# HBridge_and_Power.net
KiCad netlist of a schematic drawn in Altium Designer
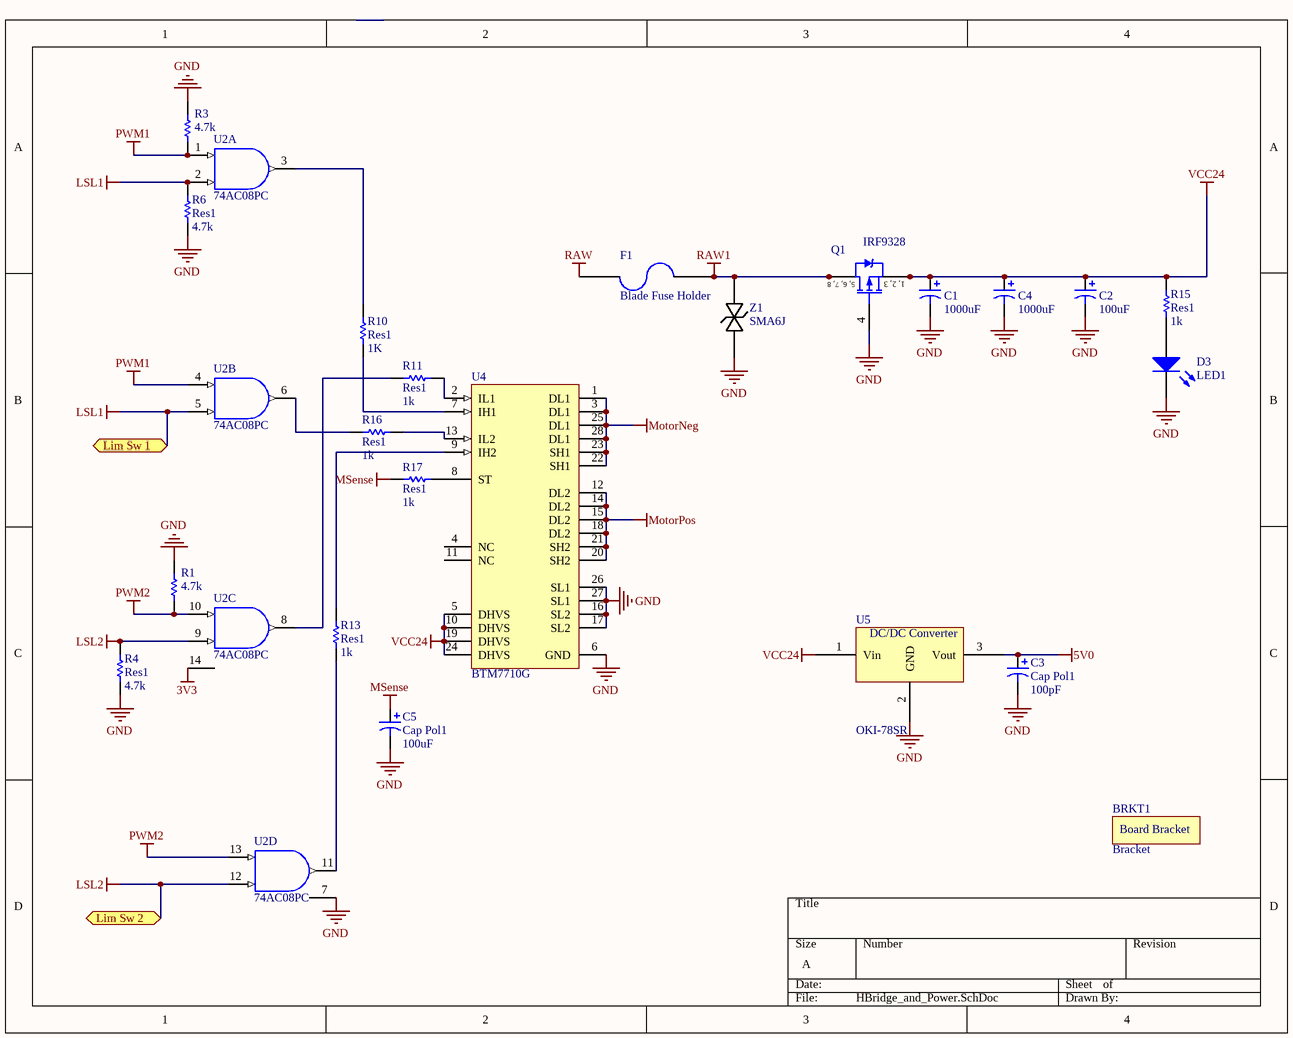
[diagram p0: HBridge_and_Power.SchDoc]

(export (version "E")
  (design (tool "Eeschema 10.0.6"))
  (components
    (comp (ref "BRKT1")
      (value "Bracket")
      (footprint "Board Bracket")
      (description "Board Bracket")
      (libsource (lib "SSS Integrated Library") (part "Bracket"))
    )
    (comp (ref "C1")
      (value "1000uF")
      (footprint "Elec. Cap 5 x 10mm")
      (description "Polarized Capacitor (Radial)")
      (fields (field (name "Comment") "Cap Pol1") (field (name "PUBLISHER") "Altium Limited"))
      (libsource (lib "Miscellaneous Devices") (part "Cap Pol1"))
    )
    (comp (ref "C2")
      (value "100uF")
      (footprint "Elec. Cap 5 x 10mm")
      (description "Polarized Capacitor (Radial)")
      (fields (field (name "Comment") "Cap Pol1") (field (name "PUBLISHER") "Altium Limited"))
      (libsource (lib "Miscellaneous Devices") (part "Cap Pol1"))
    )
    (comp (ref "C3")
      (value "Cap Pol1")
      (footprint "Elec. Cap 5 x 10mm")
      (description "Polarized Capacitor (Radial)")
      (fields (field (name "ALTIUM_VALUE") "100pF") (field (name "PUBLISHER") "Altium Limited"))
      (libsource (lib "Miscellaneous Devices") (part "Cap Pol1"))
    )
    (comp (ref "C4")
      (value "1000uF")
      (footprint "Elec. Cap 5 x 10mm")
      (description "Polarized Capacitor (Radial)")
      (fields (field (name "Comment") "Cap Pol1") (field (name "PUBLISHER") "Altium Limited"))
      (libsource (lib "Miscellaneous Devices") (part "Cap Pol1"))
    )
    (comp (ref "C5")
      (value "Cap Pol1")
      (footprint "Elec. Cap 5 x 10mm")
      (description "Polarized Capacitor (Radial)")
      (fields (field (name "ALTIUM_VALUE") "100uF") (field (name "PUBLISHER") "Altium Limited"))
      (libsource (lib "Miscellaneous Devices") (part "Cap Pol1"))
    )
    (comp (ref "D3")
      (value "LED1")
      (footprint "5mm Rad LED")
      (description "Typical RED GaAs LED")
      (fields (field (name "PUBLISHER") "Altium Limited"))
      (libsource (lib "Miscellaneous Devices") (part "LED1"))
    )
    (comp (ref "F1")
      (value "Blade Fuse Holder")
      (footprint "Fuse Holder")
      (description "PC Auto-Fuse Holder")
      (fields (field (name "MANUFACTURER") "Keystone Electronics") (field (name "PART NUMBER") "3557-15"))
      (libsource (lib "SSS Integrated Library") (part "Fuse - Auto"))
    )
    (comp (ref "Q1")
      (value "IRF9328")
      (footprint "SOIC-8")
      (description "MOSFET P-CH 30V 12A 8-SOIC")
      (libsource (lib "SSS Integrated Library") (part "IRF9328 P-FET"))
    )
    (comp (ref "R1")
      (value "4.7k")
      (footprint "AXIAL-0.3")
      (description "Resistor")
      (fields (field (name "Comment") "Res1") (field (name "PUBLISHER") "Altium Limited"))
      (libsource (lib "Miscellaneous Devices") (part "Res1"))
    )
    (comp (ref "R3")
      (value "4.7k")
      (footprint "AXIAL-0.3")
      (description "Resistor")
      (fields (field (name "Comment") "Res1") (field (name "PUBLISHER") "Altium Limited"))
      (libsource (lib "Miscellaneous Devices") (part "Res1"))
    )
    (comp (ref "R4")
      (value "Res1")
      (footprint "AXIAL-0.3")
      (description "Resistor")
      (fields (field (name "ALTIUM_VALUE") "4.7k") (field (name "PUBLISHER") "Altium Limited"))
      (libsource (lib "Miscellaneous Devices") (part "Res1"))
    )
    (comp (ref "R6")
      (value "Res1")
      (footprint "AXIAL-0.3")
      (description "Resistor")
      (fields (field (name "ALTIUM_VALUE") "4.7k") (field (name "PUBLISHER") "Altium Limited"))
      (libsource (lib "Miscellaneous Devices") (part "Res1"))
    )
    (comp (ref "R10")
      (value "Res1")
      (footprint "AXIAL-0.3")
      (description "Resistor")
      (fields (field (name "ALTIUM_VALUE") "1K") (field (name "PUBLISHER") "Altium Limited"))
      (libsource (lib "Miscellaneous Devices") (part "Res1"))
    )
    (comp (ref "R11")
      (value "Res1")
      (footprint "AXIAL-0.3")
      (description "Resistor")
      (fields (field (name "ALTIUM_VALUE") "1k") (field (name "PUBLISHER") "Altium Limited"))
      (libsource (lib "Miscellaneous Devices") (part "Res1"))
    )
    (comp (ref "R13")
      (value "Res1")
      (footprint "AXIAL-0.3")
      (description "Resistor")
      (fields (field (name "ALTIUM_VALUE") "1k") (field (name "PUBLISHER") "Altium Limited"))
      (libsource (lib "Miscellaneous Devices") (part "Res1"))
    )
    (comp (ref "R15")
      (value "Res1")
      (footprint "AXIAL-0.3")
      (description "Resistor")
      (fields (field (name "ALTIUM_VALUE") "1k") (field (name "PUBLISHER") "Altium Limited"))
      (libsource (lib "Miscellaneous Devices") (part "Res1"))
    )
    (comp (ref "R16")
      (value "Res1")
      (footprint "AXIAL-0.3")
      (description "Resistor")
      (fields (field (name "ALTIUM_VALUE") "1k") (field (name "PUBLISHER") "Altium Limited"))
      (libsource (lib "Miscellaneous Devices") (part "Res1"))
    )
    (comp (ref "R17")
      (value "Res1")
      (footprint "AXIAL-0.3")
      (description "Resistor")
      (fields (field (name "ALTIUM_VALUE") "1k") (field (name "PUBLISHER") "Altium Limited"))
      (libsource (lib "Miscellaneous Devices") (part "Res1"))
    )
    (comp (ref "U2")
      (value "74AC08PC")
      (footprint "N14A")
      (description "Quad 2-Input AND Gate, 14-Pin PDIP, Commercial Grade")
      (fields (field (name "PUBLISHER") "Altium Limited"))
      (libsource (lib "FSC Logic Gate") (part "74AC08PC"))
    )
    (comp (ref "U4")
      (value "BTM7710G")
      (footprint "INF-PG-DSO-28-22_N")
      (description "TrilithIC, 4.5 to 42 V, -40 to 150 degC, PG-DSO-28-22, Reel, Green")
      (fields (field (name "MANUFACTURER") "Infineon"))
      (libsource (lib "Infineon_Power_Motor_Driver") (part "BTM7710G"))
    )
    (comp (ref "U5")
      (value "OKI-78SR")
      (footprint "OKI-78SR")
      (description "5V DC/DC Converter (7805 replacement)")
      (libsource (lib "SSS Integrated Library") (part "7805"))
    )
    (comp (ref "Z1")
      (value "SMA6J")
      (footprint "AXIAL-0.9")
      (description "TVS DIODE 15VWM 24.4VC SMA")
      (fields (field (name "MANUFACTURER") "Micro Commercial Co") (field (name "PARTNUMBER") "SMA6J15CA-TP"))
      (libsource (lib "SSS Integrated Library") (part "Zener - Bidirectional"))
    )
  )
  (nets
    (net (code "1") (name "3V3") (class "Default")
      (node (ref "U2") (pin "14") (pinfunction "VCC_14") (pintype "power_in"))
    )
    (net (code "2") (name "5V0") (class "Default")
      (node (ref "C3") (pin "1") (pinfunction "1_1") (pintype "passive"))
      (node (ref "U5") (pin "3") (pinfunction "Vout_3") (pintype "passive"))
    )
    (net (code "3") (name "GND") (class "Default")
      (node (ref "C1") (pin "2") (pinfunction "2_2") (pintype "passive"))
      (node (ref "C2") (pin "2") (pinfunction "2_2") (pintype "passive"))
      (node (ref "C3") (pin "2") (pinfunction "2_2") (pintype "passive"))
      (node (ref "C4") (pin "2") (pinfunction "2_2") (pintype "passive"))
      (node (ref "C5") (pin "2") (pinfunction "2_2") (pintype "passive"))
      (node (ref "D3") (pin "2") (pinfunction "K_2") (pintype "passive"))
      (node (ref "Q1") (pin "4") (pinfunction "G_4") (pintype "passive"))
      (node (ref "R1") (pin "2") (pinfunction "2_2") (pintype "passive"))
      (node (ref "R3") (pin "2") (pinfunction "2_2") (pintype "passive"))
      (node (ref "R4") (pin "1") (pinfunction "1_1") (pintype "passive"))
      (node (ref "R6") (pin "1") (pinfunction "1_1") (pintype "passive"))
      (node (ref "U2") (pin "7") (pinfunction "GND_7") (pintype "power_in"))
      (node (ref "U4") (pin "16") (pinfunction "SL2_16") (pintype "power_in"))
      (node (ref "U4") (pin "17") (pinfunction "SL2_17") (pintype "power_in"))
      (node (ref "U4") (pin "26") (pinfunction "SL1_26") (pintype "power_in"))
      (node (ref "U4") (pin "27") (pinfunction "SL1_27") (pintype "power_in"))
      (node (ref "U4") (pin "6") (pinfunction "GND_6") (pintype "power_in"))
      (node (ref "U5") (pin "2") (pinfunction "GND_2") (pintype "passive"))
      (node (ref "Z1") (pin "1") (pinfunction "A_1") (pintype "passive"))
    )
    (net (code "4") (name "LSL1") (class "Default")
      (node (ref "R6") (pin "2") (pinfunction "2_2") (pintype "passive"))
      (node (ref "U2") (pin "2") (pinfunction "B_2") (pintype "input"))
      (node (ref "U2") (pin "5") (pinfunction "B_5") (pintype "input"))
    )
    (net (code "5") (name "LSL2") (class "Default")
      (node (ref "R4") (pin "2") (pinfunction "2_2") (pintype "passive"))
      (node (ref "U2") (pin "12") (pinfunction "B_12") (pintype "input"))
      (node (ref "U2") (pin "9") (pinfunction "B_9") (pintype "input"))
    )
    (net (code "6") (name "MSense") (class "Default")
      (node (ref "C5") (pin "1") (pinfunction "1_1") (pintype "passive"))
      (node (ref "R17") (pin "2") (pinfunction "2_2") (pintype "passive"))
    )
    (net (code "7") (name "MotorNeg") (class "Default")
      (node (ref "U4") (pin "1") (pinfunction "DL1_1") (pintype "power_in"))
      (node (ref "U4") (pin "22") (pinfunction "SH1_22") (pintype "power_in"))
      (node (ref "U4") (pin "23") (pinfunction "SH1_23") (pintype "power_in"))
      (node (ref "U4") (pin "25") (pinfunction "DL1_25") (pintype "power_in"))
      (node (ref "U4") (pin "28") (pinfunction "DL1_28") (pintype "power_in"))
      (node (ref "U4") (pin "3") (pinfunction "DL1_3") (pintype "power_in"))
    )
    (net (code "8") (name "MotorPos") (class "Default")
      (node (ref "U4") (pin "12") (pinfunction "DL2_12") (pintype "power_in"))
      (node (ref "U4") (pin "14") (pinfunction "DL2_14") (pintype "power_in"))
      (node (ref "U4") (pin "15") (pinfunction "DL2_15") (pintype "power_in"))
      (node (ref "U4") (pin "18") (pinfunction "DL2_18") (pintype "power_in"))
      (node (ref "U4") (pin "20") (pinfunction "SH2_20") (pintype "power_in"))
      (node (ref "U4") (pin "21") (pinfunction "SH2_21") (pintype "power_in"))
    )
    (net (code "9") (name "Net-(D3-A)") (class "Default")
      (node (ref "D3") (pin "1") (pinfunction "A_1") (pintype "passive"))
      (node (ref "R15") (pin "1") (pinfunction "1_1") (pintype "passive"))
    )
    (net (code "10") (name "Net-(U2A-O)") (class "Default")
      (node (ref "R10") (pin "2") (pinfunction "2_2") (pintype "passive"))
      (node (ref "U2") (pin "3") (pinfunction "O_3") (pintype "output"))
    )
    (net (code "11") (name "Net-(U2B-O)") (class "Default")
      (node (ref "R16") (pin "2") (pinfunction "2_2") (pintype "passive"))
      (node (ref "U2") (pin "6") (pinfunction "O_6") (pintype "output"))
    )
    (net (code "12") (name "Net-(U2C-O)") (class "Default")
      (node (ref "R11") (pin "2") (pinfunction "2_2") (pintype "passive"))
      (node (ref "U2") (pin "8") (pinfunction "O_8") (pintype "output"))
    )
    (net (code "13") (name "Net-(U2D-O)") (class "Default")
      (node (ref "R13") (pin "1") (pinfunction "1_1") (pintype "passive"))
      (node (ref "U2") (pin "11") (pinfunction "O_11") (pintype "output"))
    )
    (net (code "14") (name "Net-(U4-IH1)") (class "Default")
      (node (ref "R10") (pin "1") (pinfunction "1_1") (pintype "passive"))
      (node (ref "U4") (pin "7") (pinfunction "IH1_7") (pintype "input"))
    )
    (net (code "15") (name "Net-(U4-IH2)") (class "Default")
      (node (ref "R13") (pin "2") (pinfunction "2_2") (pintype "passive"))
      (node (ref "U4") (pin "9") (pinfunction "IH2_9") (pintype "input"))
    )
    (net (code "16") (name "Net-(U4-IL1)") (class "Default")
      (node (ref "R11") (pin "1") (pinfunction "1_1") (pintype "passive"))
      (node (ref "U4") (pin "2") (pinfunction "IL1_2") (pintype "input"))
    )
    (net (code "17") (name "Net-(U4-IL2)") (class "Default")
      (node (ref "R16") (pin "1") (pinfunction "1_1") (pintype "passive"))
      (node (ref "U4") (pin "13") (pinfunction "IL2_13") (pintype "input"))
    )
    (net (code "18") (name "Net-(U4-ST)") (class "Default")
      (node (ref "R17") (pin "1") (pinfunction "1_1") (pintype "passive"))
      (node (ref "U4") (pin "8") (pinfunction "ST_8") (pintype "open_collector"))
    )
    (net (code "19") (name "PWM1") (class "Default")
      (node (ref "R3") (pin "1") (pinfunction "1_1") (pintype "passive"))
      (node (ref "U2") (pin "1") (pinfunction "A_1") (pintype "input"))
      (node (ref "U2") (pin "4") (pinfunction "A_4") (pintype "input"))
    )
    (net (code "20") (name "PWM2") (class "Default")
      (node (ref "R1") (pin "1") (pinfunction "1_1") (pintype "passive"))
      (node (ref "U2") (pin "10") (pinfunction "A_10") (pintype "input"))
      (node (ref "U2") (pin "13") (pinfunction "A_13") (pintype "input"))
    )
    (net (code "21") (name "RAW") (class "Default")
      (node (ref "F1") (pin "1") (pinfunction "1_1") (pintype "passive"))
    )
    (net (code "22") (name "RAW1") (class "Default")
      (node (ref "F1") (pin "2") (pinfunction "2_2") (pintype "passive"))
      (node (ref "Q1") (pin "5") (pinfunction "D_5") (pintype "passive"))
      (node (ref "Q1") (pin "6") (pinfunction "D_6") (pintype "passive"))
      (node (ref "Q1") (pin "7") (pinfunction "D_7") (pintype "passive"))
      (node (ref "Q1") (pin "8") (pinfunction "D_8") (pintype "passive"))
      (node (ref "Z1") (pin "2") (pinfunction "K_2") (pintype "passive"))
    )
    (net (code "23") (name "VCC24") (class "Default")
      (node (ref "C1") (pin "1") (pinfunction "1_1") (pintype "passive"))
      (node (ref "C2") (pin "1") (pinfunction "1_1") (pintype "passive"))
      (node (ref "C4") (pin "1") (pinfunction "1_1") (pintype "passive"))
      (node (ref "Q1") (pin "1") (pinfunction "S_1") (pintype "passive"))
      (node (ref "Q1") (pin "2") (pinfunction "S_2") (pintype "passive"))
      (node (ref "Q1") (pin "3") (pinfunction "S_3") (pintype "passive"))
      (node (ref "R15") (pin "2") (pinfunction "2_2") (pintype "passive"))
      (node (ref "U4") (pin "10") (pinfunction "DHVS_10") (pintype "power_in"))
      (node (ref "U4") (pin "19") (pinfunction "DHVS_19") (pintype "power_in"))
      (node (ref "U4") (pin "24") (pinfunction "DHVS_24") (pintype "power_in"))
      (node (ref "U4") (pin "5") (pinfunction "DHVS_5") (pintype "power_in"))
      (node (ref "U5") (pin "1") (pinfunction "Vin_1") (pintype "passive"))
    )
    (net (code "24") (name "unconnected-(U4-NC-Pad4)") (class "Default")
      (node (ref "U4") (pin "4") (pinfunction "NC_4") (pintype "passive"))
    )
    (net (code "25") (name "unconnected-(U4-NC-Pad11)") (class "Default")
      (node (ref "U4") (pin "11") (pinfunction "NC_11") (pintype "passive"))
    )
  )
)
